# ShuntTripDriver.net
KiCad netlist of a schematic drawn in Altium Designer
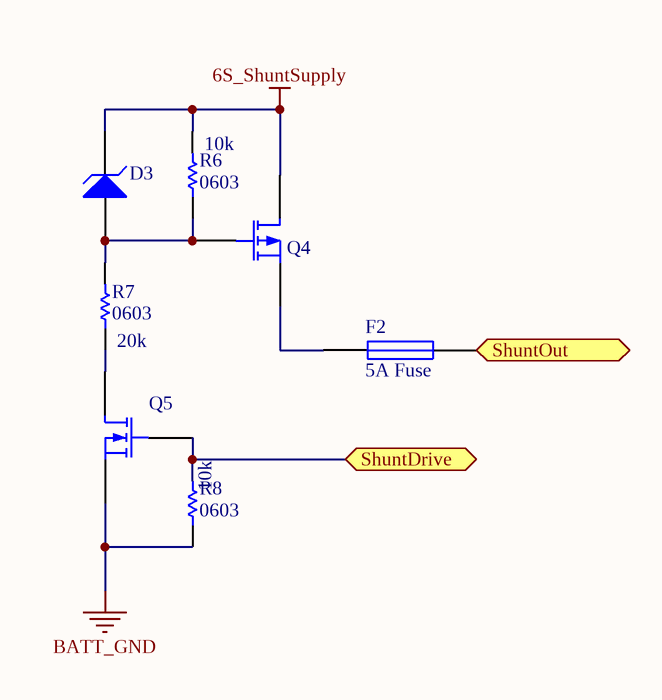
[diagram p0: ShuntTripDriver.SchDoc]

(export (version "E")
  (design (tool "Eeschema 10.0.6"))
  (components
    (comp (ref "D3")
      (value "~")
      (footprint "0805_M_POL")
      (description "Zener Diode")
      (libsource (lib "UNSW_LIB") (part "D Zener"))
    )
    (comp (ref "F2")
      (value "5A Fuse")
      (footprint "LITTELFUSE-154")
      (description "Fuse")
      (libsource (lib "Miscellaneous") (part "FUSE"))
    )
    (comp (ref "Q4")
      (value "PFET 40V 10A")
      (footprint "TO-252 (D-Pak)")
      (description "10A 40V")
      (libsource (lib "UNSW_LIB") (part "PFET 40V 10A"))
    )
    (comp (ref "Q5")
      (value "NFET 30V 5A")
      (footprint "SOT23-3")
      (libsource (lib "UNSW_LIB") (part "NFET 30V 5A"))
    )
    (comp (ref "R6")
      (value "10k")
      (footprint "0603_M")
      (description "Resistor")
      (fields (field (name "PACKAGE") "0603") (field (name "Comment") "R"))
      (libsource (lib "UNSW_LIB") (part "R"))
    )
    (comp (ref "R7")
      (value "20k")
      (footprint "0603_M")
      (description "Resistor")
      (fields (field (name "PACKAGE") "0603") (field (name "Comment") "R"))
      (libsource (lib "UNSW_LIB") (part "R"))
    )
    (comp (ref "R8")
      (value "10k")
      (footprint "0603_M")
      (description "Resistor")
      (fields (field (name "PACKAGE") "0603") (field (name "Comment") "R"))
      (libsource (lib "UNSW_LIB") (part "R"))
    )
  )
  (nets
    (net (code "1") (name "/ShuntDrive") (class "Default")
      (node (ref "Q5") (pin "1") (pinfunction "G_1") (pintype "passive"))
      (node (ref "R8") (pin "2") (pinfunction "2_2") (pintype "passive"))
    )
    (net (code "2") (name "/ShuntOut") (class "Default")
      (node (ref "F2") (pin "2") (pinfunction "2_2") (pintype "passive"))
    )
    (net (code "3") (name "6S_ShuntSupply") (class "Default")
      (node (ref "D3") (pin "2") (pinfunction "K_2") (pintype "passive"))
      (node (ref "Q4") (pin "1") (pinfunction "D_1") (pintype "passive"))
      (node (ref "R6") (pin "2") (pinfunction "2_2") (pintype "passive"))
    )
    (net (code "4") (name "BATT_GND") (class "Default")
      (node (ref "Q5") (pin "2") (pinfunction "S_2") (pintype "passive"))
      (node (ref "R8") (pin "1") (pinfunction "1_1") (pintype "passive"))
    )
    (net (code "5") (name "Net-(D3-A)") (class "Default")
      (node (ref "D3") (pin "1") (pinfunction "A_1") (pintype "passive"))
      (node (ref "Q4") (pin "2") (pinfunction "G_2") (pintype "passive"))
      (node (ref "R6") (pin "1") (pinfunction "1_1") (pintype "passive"))
      (node (ref "R7") (pin "2") (pinfunction "2_2") (pintype "passive"))
    )
    (net (code "6") (name "Net-(Q4-S)") (class "Default")
      (node (ref "F2") (pin "1") (pinfunction "1_1") (pintype "passive"))
      (node (ref "Q4") (pin "3") (pinfunction "S_3") (pintype "passive"))
    )
    (net (code "7") (name "Net-(Q5-D)") (class "Default")
      (node (ref "Q5") (pin "3") (pinfunction "D_3") (pintype "passive"))
      (node (ref "R7") (pin "1") (pinfunction "1_1") (pintype "passive"))
    )
  )
)
